# SparkFun_Pro_Micro.net
KiCad netlist of a schematic drawn in EAGLE
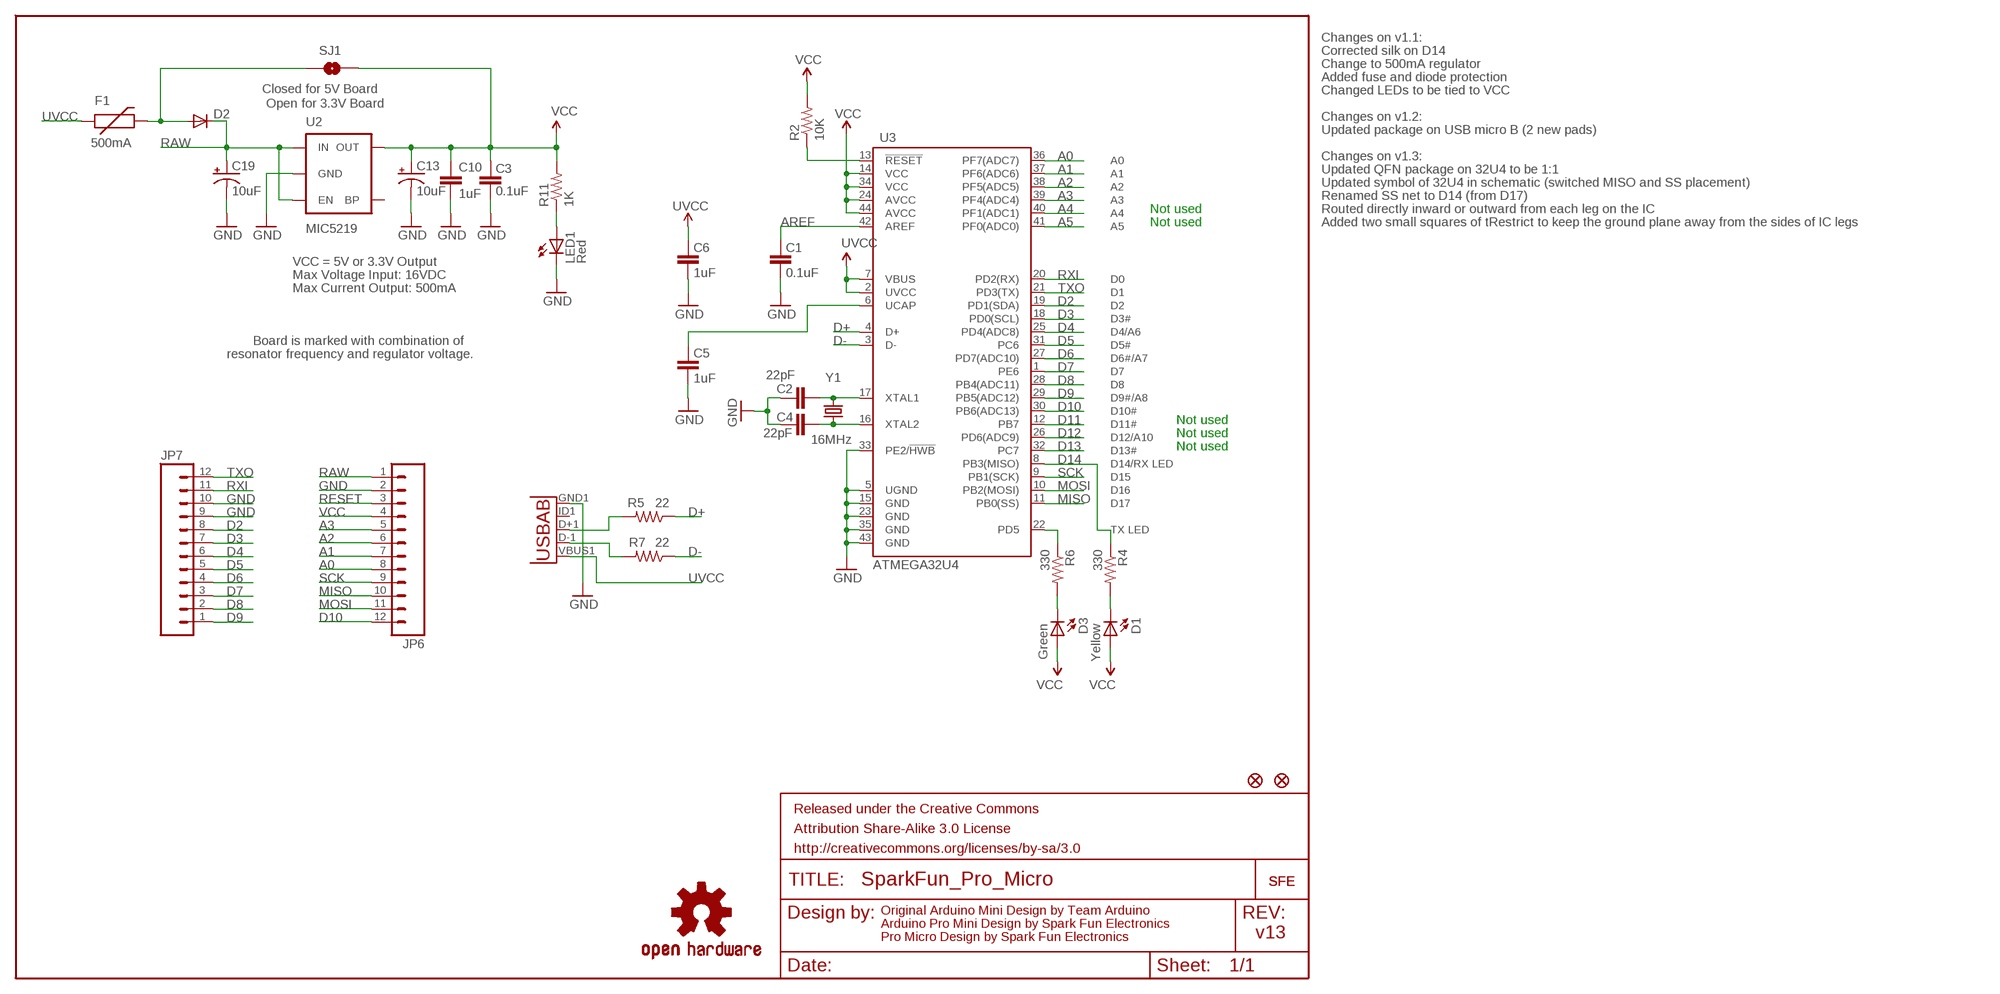
[diagram p0: schematic, sheet 1]

(export (version "E")
  (design (tool "Eeschema 10.0.6"))
  (components
    (comp (ref "C1")
      (value "0.1uF")
      (footprint "eagle-import:0603-CAP")
      (libsource (lib "eagle-import") (part "CAP0603-CAP"))
    )
    (comp (ref "C2")
      (value "22pF")
      (footprint "eagle-import:0603-CAP")
      (libsource (lib "eagle-import") (part "CAP0603-CAP"))
    )
    (comp (ref "C3")
      (value "0.1uF")
      (footprint "eagle-import:0603-CAP")
      (libsource (lib "eagle-import") (part "CAP0603-CAP"))
    )
    (comp (ref "C4")
      (value "22pF")
      (footprint "eagle-import:0603-CAP")
      (libsource (lib "eagle-import") (part "CAP0603-CAP"))
    )
    (comp (ref "C5")
      (value "1uF")
      (footprint "eagle-import:0603-CAP")
      (libsource (lib "eagle-import") (part "CAP0603-CAP"))
    )
    (comp (ref "C6")
      (value "1uF")
      (footprint "eagle-import:0603-CAP")
      (libsource (lib "eagle-import") (part "CAP0603-CAP"))
    )
    (comp (ref "C10")
      (value "1uF")
      (footprint "eagle-import:0603-CAP")
      (libsource (lib "eagle-import") (part "CAP0603-CAP"))
    )
    (comp (ref "C13")
      (value "10uF")
      (footprint "eagle-import:EIA3216")
      (libsource (lib "eagle-import") (part "CAP_POL1206"))
    )
    (comp (ref "C19")
      (value "10uF")
      (footprint "eagle-import:EIA3216")
      (libsource (lib "eagle-import") (part "CAP_POL1206"))
    )
    (comp (ref "D1")
      (value "Yellow")
      (footprint "eagle-import:LED-0603")
      (libsource (lib "eagle-import") (part "LED0603"))
    )
    (comp (ref "D2")
      (value "DIODESOD")
      (footprint "eagle-import:SOD-323")
      (libsource (lib "eagle-import") (part "DIODESOD"))
    )
    (comp (ref "D3")
      (value "Green")
      (footprint "eagle-import:LED-0603")
      (libsource (lib "eagle-import") (part "LED0603"))
    )
    (comp (ref "F1")
      (value "500mA")
      (footprint "eagle-import:PTC-1206")
      (libsource (lib "eagle-import") (part "PTCSMD"))
    )
    (comp (ref "FRAME1")
      (value "FRAME-LETTER")
      (footprint "eagle-import:CREATIVE_COMMONS")
      (libsource (lib "eagle-import") (part "FRAME-LETTER"))
    )
    (comp (ref "JP1")
      (value "FIDUCIALUFIDUCIAL")
      (footprint "eagle-import:MICRO-FIDUCIAL")
      (libsource (lib "eagle-import") (part "FIDUCIALUFIDUCIAL"))
    )
    (comp (ref "JP2")
      (value "FIDUCIALUFIDUCIAL")
      (footprint "eagle-import:MICRO-FIDUCIAL")
      (libsource (lib "eagle-import") (part "FIDUCIALUFIDUCIAL"))
    )
    (comp (ref "JP6")
      (value "M12PTH")
      (footprint "eagle-import:1X12")
      (libsource (lib "eagle-import") (part "M12PTH"))
    )
    (comp (ref "JP7")
      (value "M12PTH")
      (footprint "eagle-import:1X12")
      (libsource (lib "eagle-import") (part "M12PTH"))
    )
    (comp (ref "LED1")
      (value "Red")
      (footprint "eagle-import:LED-0603")
      (libsource (lib "eagle-import") (part "LED0603"))
    )
    (comp (ref "R2")
      (value "10K")
      (footprint "eagle-import:0603-RES")
      (libsource (lib "eagle-import") (part "RESISTOR0603-RES"))
    )
    (comp (ref "R4")
      (value "330")
      (footprint "eagle-import:0603-RES")
      (libsource (lib "eagle-import") (part "RESISTOR0603-RES"))
    )
    (comp (ref "R5")
      (value "22")
      (footprint "eagle-import:0603-RES")
      (libsource (lib "eagle-import") (part "RESISTOR0603-RES"))
    )
    (comp (ref "R6")
      (value "330")
      (footprint "eagle-import:0603-RES")
      (libsource (lib "eagle-import") (part "RESISTOR0603-RES"))
    )
    (comp (ref "R7")
      (value "22")
      (footprint "eagle-import:0603-RES")
      (libsource (lib "eagle-import") (part "RESISTOR0603-RES"))
    )
    (comp (ref "R11")
      (value "1K")
      (footprint "eagle-import:0603-RES")
      (libsource (lib "eagle-import") (part "RESISTOR0603-RES"))
    )
    (comp (ref "SJ1")
      (value "Closed for 5V Board")
      (footprint "eagle-import:SJ_2S")
      (libsource (lib "eagle-import") (part "SOLDERJUMPERNC"))
    )
    (comp (ref "U$1")
      (value "LOGO-SFESK")
      (footprint "eagle-import:SFE-LOGO-FLAME")
      (libsource (lib "eagle-import") (part "LOGO-SFESK"))
    )
    (comp (ref "U$3")
      (value "OSHW-LOGOS")
      (footprint "eagle-import:OSHW-LOGO-S")
      (libsource (lib "eagle-import") (part "OSHW-LOGOS"))
    )
    (comp (ref "U$11")
      (value "LOGO-SFENEW")
      (footprint "eagle-import:SFE-NEW-WEBLOGO")
      (libsource (lib "eagle-import") (part "LOGO-SFENEW"))
    )
    (comp (ref "U2")
      (value "MIC5219")
      (footprint "eagle-import:SOT23-5")
      (libsource (lib "eagle-import") (part "V_REG_LDOSMD"))
    )
    (comp (ref "U3")
      (value "ATMEGA32U4")
      (footprint "eagle-import:QFN-44-NOPAD_1_1-OUTFAKES")
      (libsource (lib "eagle-import") (part "ATMEGA32U4OUTFAKES"))
    )
    (comp (ref "X1")
      (value "USB-ABIN&OUT")
      (footprint "eagle-import:USB-AB-MICRO-SMD-V03-IN&OUT")
      (libsource (lib "eagle-import") (part "USB-ABIN&OUT"))
    )
    (comp (ref "Y1")
      (value "16MHz")
      (footprint "eagle-import:CRYSTAL-SMD-5X3")
      (libsource (lib "eagle-import") (part "CRYSTAL5X3"))
    )
  )
  (nets
    (net (code "1") (name "/A0") (class "Default")
      (node (ref "JP6") (pin "8") (pinfunction "8_8") (pintype "passive"))
      (node (ref "U3") (pin "36") (pinfunction "PF7(ADC7)_36") (pintype "bidirectional"))
    )
    (net (code "2") (name "/A1") (class "Default")
      (node (ref "JP6") (pin "7") (pinfunction "7_7") (pintype "passive"))
      (node (ref "U3") (pin "37") (pinfunction "PF6(ADC6)_37") (pintype "bidirectional"))
    )
    (net (code "3") (name "/A2") (class "Default")
      (node (ref "JP6") (pin "6") (pinfunction "6_6") (pintype "passive"))
      (node (ref "U3") (pin "38") (pinfunction "PF5(ADC5)_38") (pintype "bidirectional"))
    )
    (net (code "4") (name "/A3") (class "Default")
      (node (ref "JP6") (pin "5") (pinfunction "5_5") (pintype "passive"))
      (node (ref "U3") (pin "39") (pinfunction "PF4(ADC4)_39") (pintype "bidirectional"))
    )
    (net (code "5") (name "/A4") (class "Default")
      (node (ref "U3") (pin "40") (pinfunction "PF1(ADC1)_40") (pintype "bidirectional"))
    )
    (net (code "6") (name "/A5") (class "Default")
      (node (ref "U3") (pin "41") (pinfunction "PF0(ADC0)_41") (pintype "bidirectional"))
    )
    (net (code "7") (name "/AREF") (class "Default")
      (node (ref "C1") (pin "2") (pinfunction "2_2") (pintype "passive"))
      (node (ref "U3") (pin "42") (pinfunction "AREF_42") (pintype "bidirectional"))
    )
    (net (code "8") (name "/D+") (class "Default")
      (node (ref "R5") (pin "1") (pinfunction "1_1") (pintype "passive"))
      (node (ref "U3") (pin "4") (pinfunction "D+_4") (pintype "bidirectional"))
    )
    (net (code "9") (name "/D-") (class "Default")
      (node (ref "R7") (pin "1") (pinfunction "1_1") (pintype "passive"))
      (node (ref "U3") (pin "3") (pinfunction "D-_3") (pintype "bidirectional"))
    )
    (net (code "10") (name "/D2") (class "Default")
      (node (ref "JP7") (pin "8") (pinfunction "8_8") (pintype "passive"))
      (node (ref "U3") (pin "19") (pinfunction "PD1(SDA)_19") (pintype "bidirectional"))
    )
    (net (code "11") (name "/D3") (class "Default")
      (node (ref "JP7") (pin "7") (pinfunction "7_7") (pintype "passive"))
      (node (ref "U3") (pin "18") (pinfunction "PD0(SCL)_18") (pintype "bidirectional"))
    )
    (net (code "12") (name "/D4") (class "Default")
      (node (ref "JP7") (pin "6") (pinfunction "6_6") (pintype "passive"))
      (node (ref "U3") (pin "25") (pinfunction "PD4(ADC8)_25") (pintype "bidirectional"))
    )
    (net (code "13") (name "/D5") (class "Default")
      (node (ref "JP7") (pin "5") (pinfunction "5_5") (pintype "passive"))
      (node (ref "U3") (pin "31") (pinfunction "PC6_31") (pintype "bidirectional"))
    )
    (net (code "14") (name "/D6") (class "Default")
      (node (ref "JP7") (pin "4") (pinfunction "4_4") (pintype "passive"))
      (node (ref "U3") (pin "27") (pinfunction "PD7(ADC10)_27") (pintype "bidirectional"))
    )
    (net (code "15") (name "/D7") (class "Default")
      (node (ref "JP7") (pin "3") (pinfunction "3_3") (pintype "passive"))
      (node (ref "U3") (pin "1") (pinfunction "PE6_1") (pintype "bidirectional"))
    )
    (net (code "16") (name "/D8") (class "Default")
      (node (ref "JP7") (pin "2") (pinfunction "2_2") (pintype "passive"))
      (node (ref "U3") (pin "28") (pinfunction "PB4(ADC11)_28") (pintype "bidirectional"))
    )
    (net (code "17") (name "/D9") (class "Default")
      (node (ref "JP7") (pin "1") (pinfunction "1_1") (pintype "passive"))
      (node (ref "U3") (pin "29") (pinfunction "PB5(ADC12)_29") (pintype "bidirectional"))
    )
    (net (code "18") (name "/D10") (class "Default")
      (node (ref "JP6") (pin "12") (pinfunction "12_12") (pintype "passive"))
      (node (ref "U3") (pin "30") (pinfunction "PB6(ADC13)_30") (pintype "bidirectional"))
    )
    (net (code "19") (name "/D11") (class "Default")
      (node (ref "U3") (pin "12") (pinfunction "PB7_12") (pintype "bidirectional"))
    )
    (net (code "20") (name "/D12") (class "Default")
      (node (ref "U3") (pin "26") (pinfunction "PD6(ADC9)_26") (pintype "bidirectional"))
    )
    (net (code "21") (name "/D13") (class "Default")
      (node (ref "U3") (pin "32") (pinfunction "PC7_32") (pintype "bidirectional"))
    )
    (net (code "22") (name "/D14") (class "Default")
      (node (ref "R4") (pin "1") (pinfunction "1_1") (pintype "passive"))
      (node (ref "U3") (pin "8") (pinfunction "PB3(MISO)_8") (pintype "bidirectional"))
    )
    (net (code "23") (name "/MISO") (class "Default")
      (node (ref "JP6") (pin "10") (pinfunction "10_10") (pintype "passive"))
      (node (ref "U3") (pin "11") (pinfunction "PB0(SS)_11") (pintype "bidirectional"))
    )
    (net (code "24") (name "/MOSI") (class "Default")
      (node (ref "JP6") (pin "11") (pinfunction "11_11") (pintype "passive"))
      (node (ref "U3") (pin "10") (pinfunction "PB2(MOSI)_10") (pintype "bidirectional"))
    )
    (net (code "25") (name "/RAW") (class "Default")
      (node (ref "C19") (pin "A") (pinfunction "+_A") (pintype "passive"))
      (node (ref "D2") (pin "1") (pinfunction "C_1") (pintype "passive"))
      (node (ref "JP6") (pin "1") (pinfunction "1_1") (pintype "passive"))
      (node (ref "U2") (pin "1") (pinfunction "IN_1") (pintype "input"))
      (node (ref "U2") (pin "3") (pinfunction "EN_3") (pintype "input"))
    )
    (net (code "26") (name "/RESET") (class "Default")
      (node (ref "JP6") (pin "3") (pinfunction "3_3") (pintype "passive"))
      (node (ref "R2") (pin "1") (pinfunction "1_1") (pintype "passive"))
      (node (ref "U3") (pin "13") (pinfunction "~{RESET}_13") (pintype "bidirectional"))
    )
    (net (code "27") (name "/RXI") (class "Default")
      (node (ref "JP7") (pin "11") (pinfunction "11_11") (pintype "passive"))
      (node (ref "U3") (pin "20") (pinfunction "PD2(RX)_20") (pintype "bidirectional"))
    )
    (net (code "28") (name "/SCK") (class "Default")
      (node (ref "JP6") (pin "9") (pinfunction "9_9") (pintype "passive"))
      (node (ref "U3") (pin "9") (pinfunction "PB1(SCK)_9") (pintype "bidirectional"))
    )
    (net (code "29") (name "/TXO") (class "Default")
      (node (ref "JP7") (pin "12") (pinfunction "12_12") (pintype "passive"))
      (node (ref "U3") (pin "21") (pinfunction "PD3(TX)_21") (pintype "bidirectional"))
    )
    (net (code "30") (name "GND") (class "Default")
      (node (ref "C1") (pin "1") (pinfunction "1_1") (pintype "passive"))
      (node (ref "C10") (pin "2") (pinfunction "2_2") (pintype "passive"))
      (node (ref "C13") (pin "C") (pinfunction "-_C") (pintype "passive"))
      (node (ref "C19") (pin "C") (pinfunction "-_C") (pintype "passive"))
      (node (ref "C2") (pin "2") (pinfunction "2_2") (pintype "passive"))
      (node (ref "C3") (pin "1") (pinfunction "1_1") (pintype "passive"))
      (node (ref "C4") (pin "2") (pinfunction "2_2") (pintype "passive"))
      (node (ref "C5") (pin "1") (pinfunction "1_1") (pintype "passive"))
      (node (ref "C6") (pin "1") (pinfunction "1_1") (pintype "passive"))
      (node (ref "JP6") (pin "2") (pinfunction "2_2") (pintype "passive"))
      (node (ref "JP7") (pin "10") (pinfunction "10_10") (pintype "passive"))
      (node (ref "JP7") (pin "9") (pinfunction "9_9") (pintype "passive"))
      (node (ref "LED1") (pin "C") (pinfunction "C_C") (pintype "passive"))
      (node (ref "U2") (pin "2") (pinfunction "GND_2") (pintype "input"))
      (node (ref "U3") (pin "15") (pinfunction "GND_15") (pintype "bidirectional"))
      (node (ref "U3") (pin "23") (pinfunction "GND_23") (pintype "bidirectional"))
      (node (ref "U3") (pin "33") (pinfunction "PE2/~{HWB}_33") (pintype "bidirectional"))
      (node (ref "U3") (pin "35") (pinfunction "GND_35") (pintype "bidirectional"))
      (node (ref "U3") (pin "43") (pinfunction "GND_43") (pintype "bidirectional"))
      (node (ref "U3") (pin "5") (pinfunction "UGND_5") (pintype "bidirectional"))
      (node (ref "X1") (pin "GND1") (pinfunction "GND_GND1") (pintype "bidirectional"))
    )
    (net (code "31") (name "Net-(D1-PadC)") (class "Default")
      (node (ref "D1") (pin "C") (pinfunction "C_C") (pintype "passive"))
      (node (ref "R4") (pin "2") (pinfunction "2_2") (pintype "passive"))
    )
    (net (code "32") (name "Net-(D2-A)") (class "Default")
      (node (ref "D2") (pin "2") (pinfunction "A_2") (pintype "passive"))
      (node (ref "F1") (pin "2") (pinfunction "2_2") (pintype "bidirectional"))
      (node (ref "SJ1") (pin "1") (pinfunction "1_1") (pintype "passive"))
    )
    (net (code "33") (name "Net-(D3-PadC)") (class "Default")
      (node (ref "D3") (pin "C") (pinfunction "C_C") (pintype "passive"))
      (node (ref "R6") (pin "2") (pinfunction "2_2") (pintype "passive"))
    )
    (net (code "34") (name "Net-(LED1-PadA)") (class "Default")
      (node (ref "LED1") (pin "A") (pinfunction "A_A") (pintype "passive"))
      (node (ref "R11") (pin "1") (pinfunction "1_1") (pintype "passive"))
    )
    (net (code "35") (name "Net-(U3-PD5)") (class "Default")
      (node (ref "R6") (pin "1") (pinfunction "1_1") (pintype "passive"))
      (node (ref "U3") (pin "22") (pinfunction "PD5_22") (pintype "bidirectional"))
    )
    (net (code "36") (name "Net-(U3-UCAP)") (class "Default")
      (node (ref "C5") (pin "2") (pinfunction "2_2") (pintype "passive"))
      (node (ref "U3") (pin "6") (pinfunction "UCAP_6") (pintype "bidirectional"))
    )
    (net (code "37") (name "Net-(U3-XTAL1)") (class "Default")
      (node (ref "C2") (pin "1") (pinfunction "1_1") (pintype "passive"))
      (node (ref "U3") (pin "17") (pinfunction "XTAL1_17") (pintype "bidirectional"))
      (node (ref "Y1") (pin "3") (pinfunction "2_3") (pintype "passive"))
    )
    (net (code "38") (name "Net-(U3-XTAL2)") (class "Default")
      (node (ref "C4") (pin "1") (pinfunction "1_1") (pintype "passive"))
      (node (ref "U3") (pin "16") (pinfunction "XTAL2_16") (pintype "bidirectional"))
      (node (ref "Y1") (pin "1") (pinfunction "1_1") (pintype "passive"))
    )
    (net (code "39") (name "Net-(X1-D+)") (class "Default")
      (node (ref "R5") (pin "2") (pinfunction "2_2") (pintype "passive"))
      (node (ref "X1") (pin "D+1") (pinfunction "D+_D+1") (pintype "bidirectional"))
    )
    (net (code "40") (name "Net-(X1-D-)") (class "Default")
      (node (ref "R7") (pin "2") (pinfunction "2_2") (pintype "passive"))
      (node (ref "X1") (pin "D-1") (pinfunction "D-_D-1") (pintype "bidirectional"))
    )
    (net (code "41") (name "UVCC") (class "Default")
      (node (ref "C6") (pin "2") (pinfunction "2_2") (pintype "passive"))
      (node (ref "F1") (pin "1") (pinfunction "1_1") (pintype "bidirectional"))
      (node (ref "U3") (pin "2") (pinfunction "UVCC_2") (pintype "bidirectional"))
      (node (ref "U3") (pin "7") (pinfunction "VBUS_7") (pintype "bidirectional"))
      (node (ref "X1") (pin "VBUS1") (pinfunction "VBUS_VBUS1") (pintype "bidirectional"))
    )
    (net (code "42") (name "VCC") (class "Default")
      (node (ref "C10") (pin "1") (pinfunction "1_1") (pintype "passive"))
      (node (ref "C13") (pin "A") (pinfunction "+_A") (pintype "passive"))
      (node (ref "C3") (pin "2") (pinfunction "2_2") (pintype "passive"))
      (node (ref "D1") (pin "A") (pinfunction "A_A") (pintype "passive"))
      (node (ref "D3") (pin "A") (pinfunction "A_A") (pintype "passive"))
      (node (ref "JP6") (pin "4") (pinfunction "4_4") (pintype "passive"))
      (node (ref "R11") (pin "2") (pinfunction "2_2") (pintype "passive"))
      (node (ref "R2") (pin "2") (pinfunction "2_2") (pintype "passive"))
      (node (ref "SJ1") (pin "2") (pinfunction "2_2") (pintype "passive"))
      (node (ref "U2") (pin "5") (pinfunction "OUT_5") (pintype "passive"))
      (node (ref "U3") (pin "14") (pinfunction "VCC_14") (pintype "bidirectional"))
      (node (ref "U3") (pin "24") (pinfunction "AVCC_24") (pintype "bidirectional"))
      (node (ref "U3") (pin "34") (pinfunction "VCC_34") (pintype "bidirectional"))
      (node (ref "U3") (pin "44") (pinfunction "AVCC_44") (pintype "bidirectional"))
    )
    (net (code "43") (name "unconnected-(U2-BP-Pad4)") (class "Default")
      (node (ref "U2") (pin "4") (pinfunction "BP_4") (pintype "input"))
    )
    (net (code "44") (name "unconnected-(X1-USBID-PadID1)") (class "Default")
      (node (ref "X1") (pin "ID1") (pinfunction "USBID_ID1") (pintype "bidirectional"))
    )
  )
)
